# schematic.net
KiCad netlist of a schematic drawn in EasyEDA
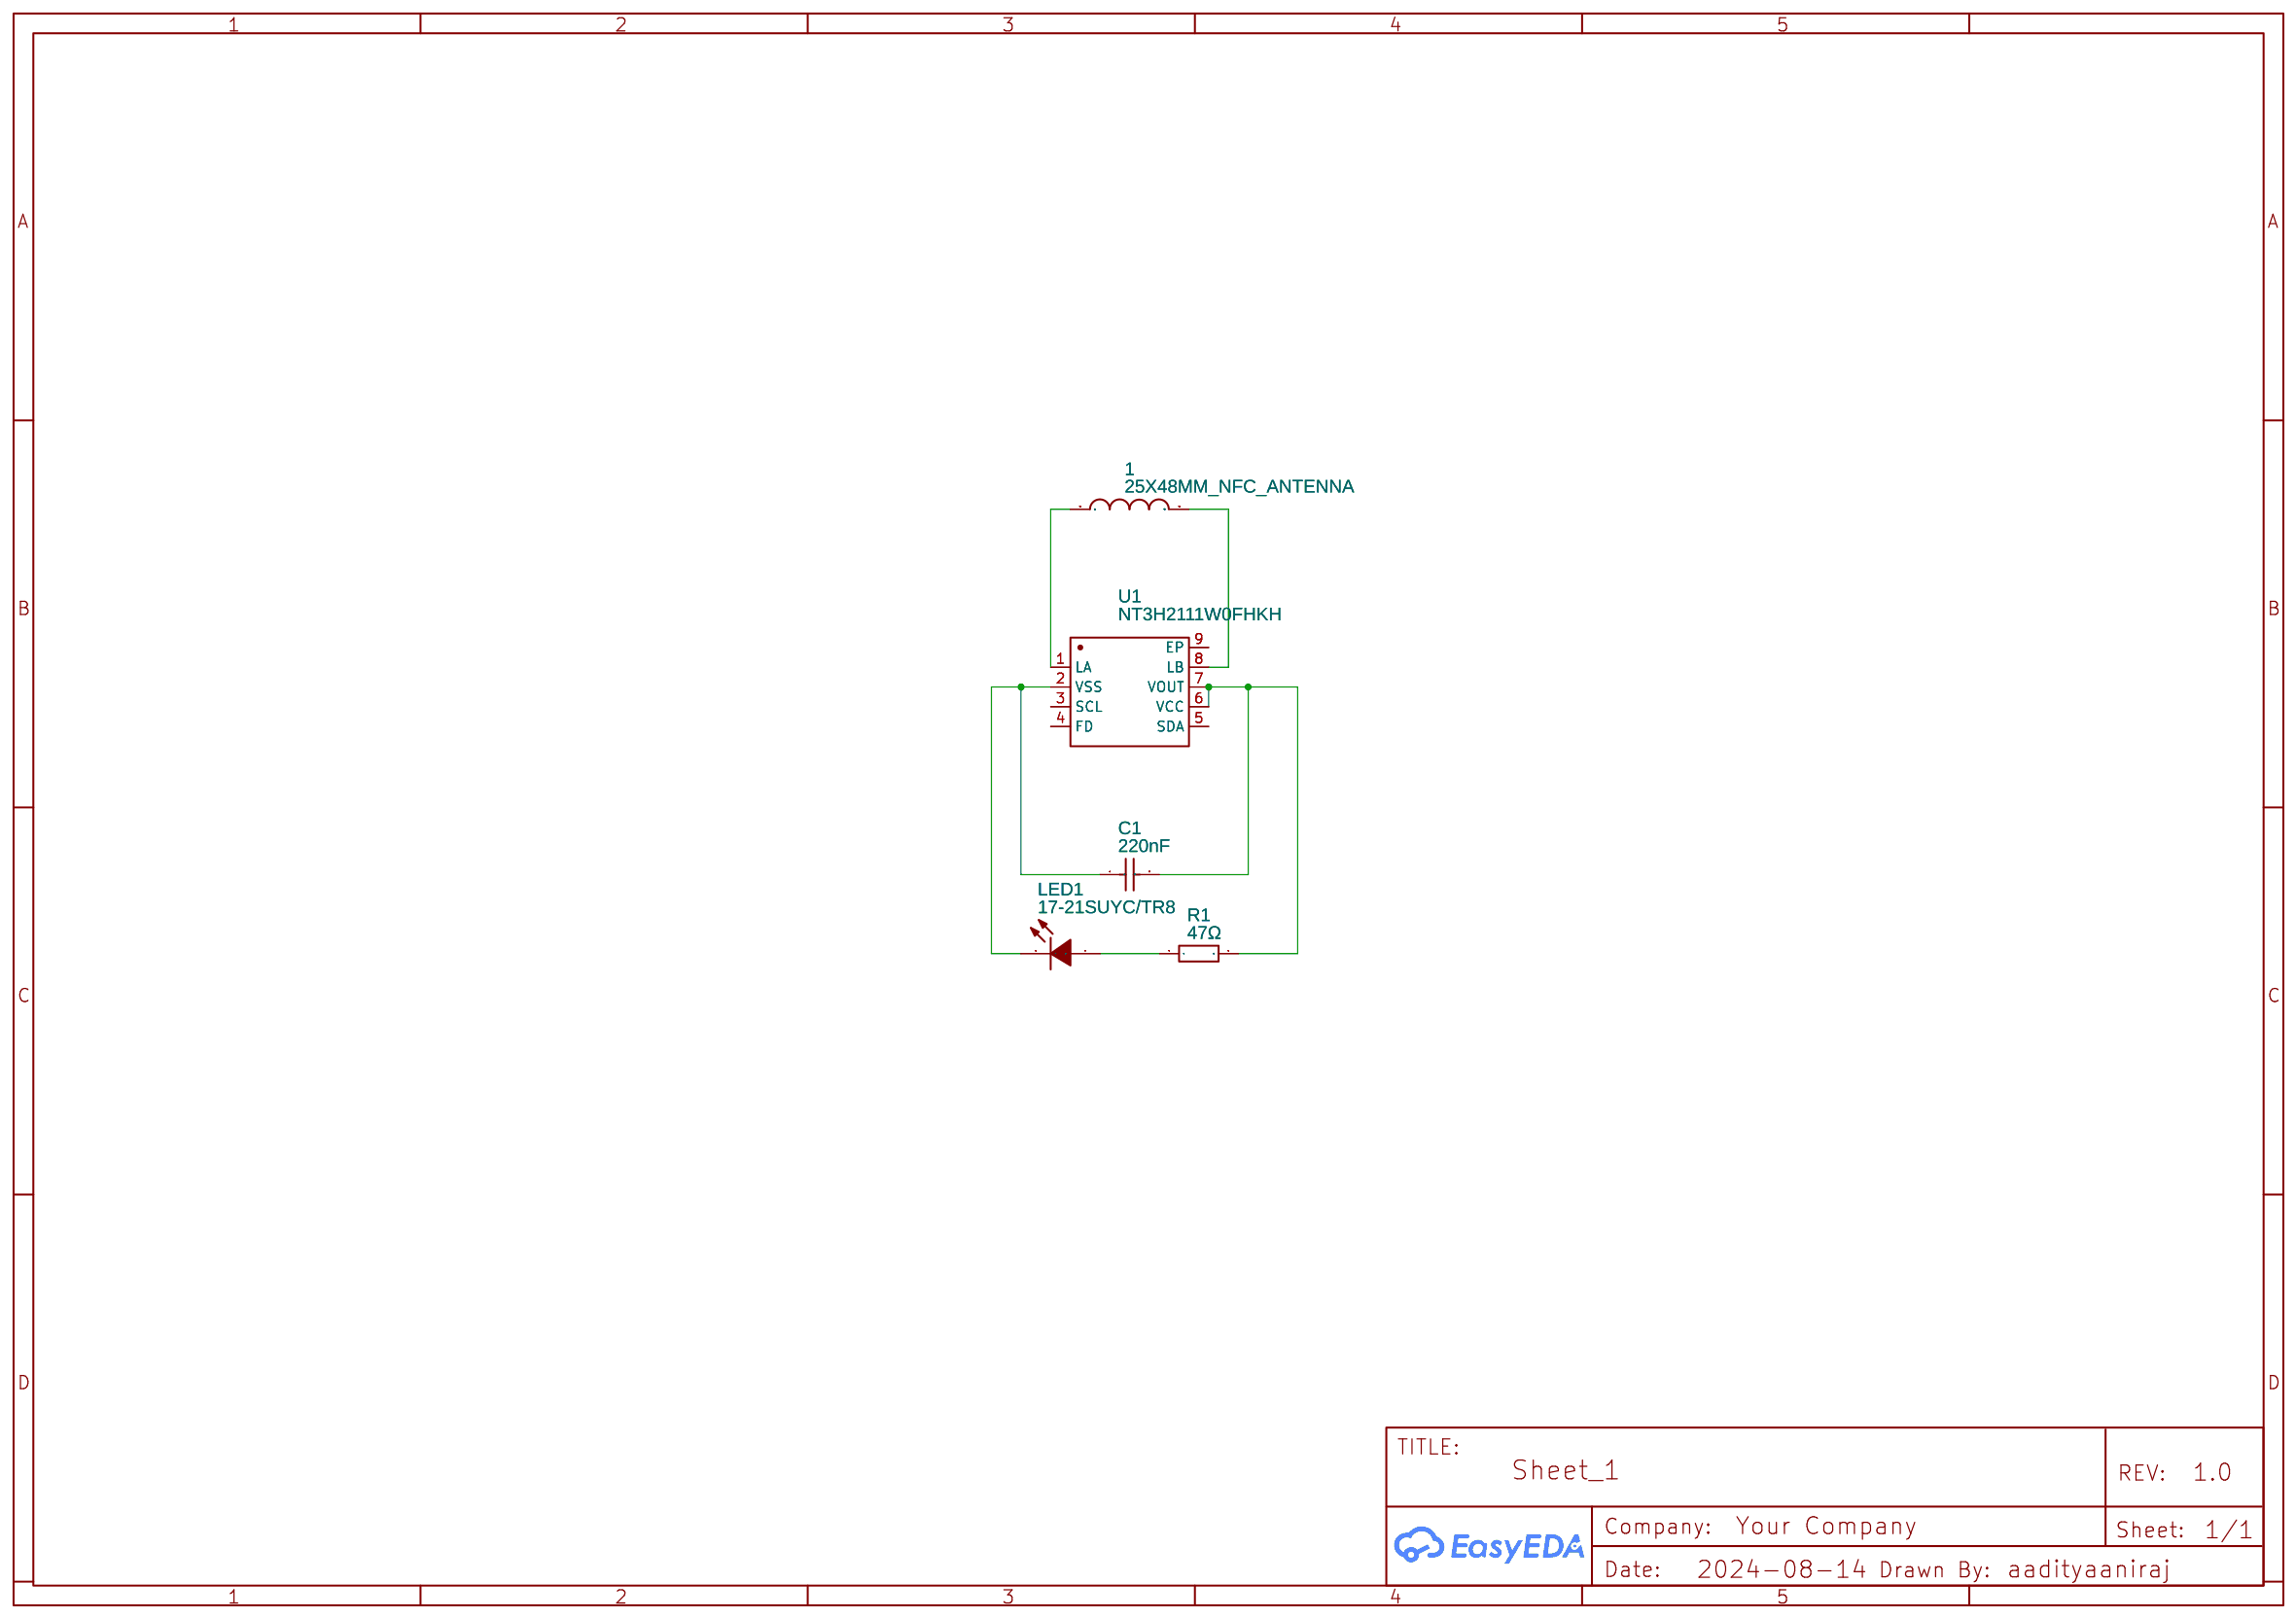
[diagram p0: schematic sheet]

(export (version "E")
  (design (tool "Eeschema 10.0.6"))
  (components
    (comp (ref "1") (value "25X48MM_NFC_ANTENNA") (libsource (lib "") (part "25X48MM_NFC_ANTENNA")))
    (comp (ref "C1")
      (value "220nF")
      (fields
        (field (name "Manufacturer Part") "CL10B224KA8NNNC")
        (field (name "Manufacturer") "SAMSUNG(三星)")
      )
      (libsource (lib "") (part "CL10B224KA8NNNC"))
    )
    (comp (ref "LED1")
      (value "17-21SUYC/TR8")
      (fields (field (name "Manufacturer Part") "KT-0805黄灯") (field (name "Manufacturer") "KENTO"))
      (libsource (lib "") (part "17-21SUYC/TR8"))
    )
    (comp (ref "R1")
      (value "47Ω")
      (fields
        (field (name "Manufacturer Part") "0603WAF470JT5E")
        (field (name "Manufacturer") "UNI-ROYAL(厚声)")
      )
      (libsource (lib "") (part "0603WAF470JT5E"))
    )
    (comp (ref "U1")
      (value "NT3H2111W0FHKH")
      (fields (field (name "Manufacturer") "NXP(恩智浦)"))
      (libsource (lib "") (part "NT3H2111W0FHKH"))
    )
  )
  (nets
    (net (code "1") (name "Net-(LED1-+)") (class "Default")
      (node (ref "LED1") (pin "1") (pinfunction "+_1") (pintype "unspecified"))
      (node (ref "R1") (pin "1") (pinfunction "1_1") (pintype "input"))
    )
    (net (code "2") (name "Net-(LED1--)") (class "Default")
      (node (ref "C1") (pin "1") (pinfunction "1_1") (pintype "input"))
      (node (ref "LED1") (pin "2") (pinfunction "-_2") (pintype "unspecified"))
      (node (ref "U1") (pin "2") (pinfunction "VSS_2") (pintype "unspecified"))
    )
    (net (code "3") (name "Net-(U1-LA)") (class "Default")
      (node (ref "1") (pin "P$1") (pinfunction "P$1_P$1") (pintype "bidirectional"))
      (node (ref "U1") (pin "1") (pinfunction "LA_1") (pintype "unspecified"))
    )
    (net (code "4") (name "Net-(U1-LB)") (class "Default")
      (node (ref "1") (pin "P$2") (pinfunction "P$2_P$2") (pintype "bidirectional"))
      (node (ref "U1") (pin "8") (pinfunction "LB_8") (pintype "unspecified"))
    )
    (net (code "5") (name "Net-(U1-VCC)") (class "Default")
      (node (ref "C1") (pin "2") (pinfunction "2_2") (pintype "input"))
      (node (ref "R1") (pin "2") (pinfunction "2_2") (pintype "input"))
      (node (ref "U1") (pin "6") (pinfunction "VCC_6") (pintype "unspecified"))
      (node (ref "U1") (pin "7") (pinfunction "VOUT_7") (pintype "unspecified"))
    )
    (net (code "6") (name "unconnected-(U1-EP-Pad9)") (class "Default")
      (node (ref "U1") (pin "9") (pinfunction "EP_9") (pintype "unspecified"))
    )
    (net (code "7") (name "unconnected-(U1-FD-Pad4)") (class "Default")
      (node (ref "U1") (pin "4") (pinfunction "FD_4") (pintype "unspecified"))
    )
    (net (code "8") (name "unconnected-(U1-SCL-Pad3)") (class "Default")
      (node (ref "U1") (pin "3") (pinfunction "SCL_3") (pintype "unspecified"))
    )
    (net (code "9") (name "unconnected-(U1-SDA-Pad5)") (class "Default")
      (node (ref "U1") (pin "5") (pinfunction "SDA_5") (pintype "unspecified"))
    )
  )
)
